# blous-afich.net
KiCad netlist of a schematic drawn in EAGLE
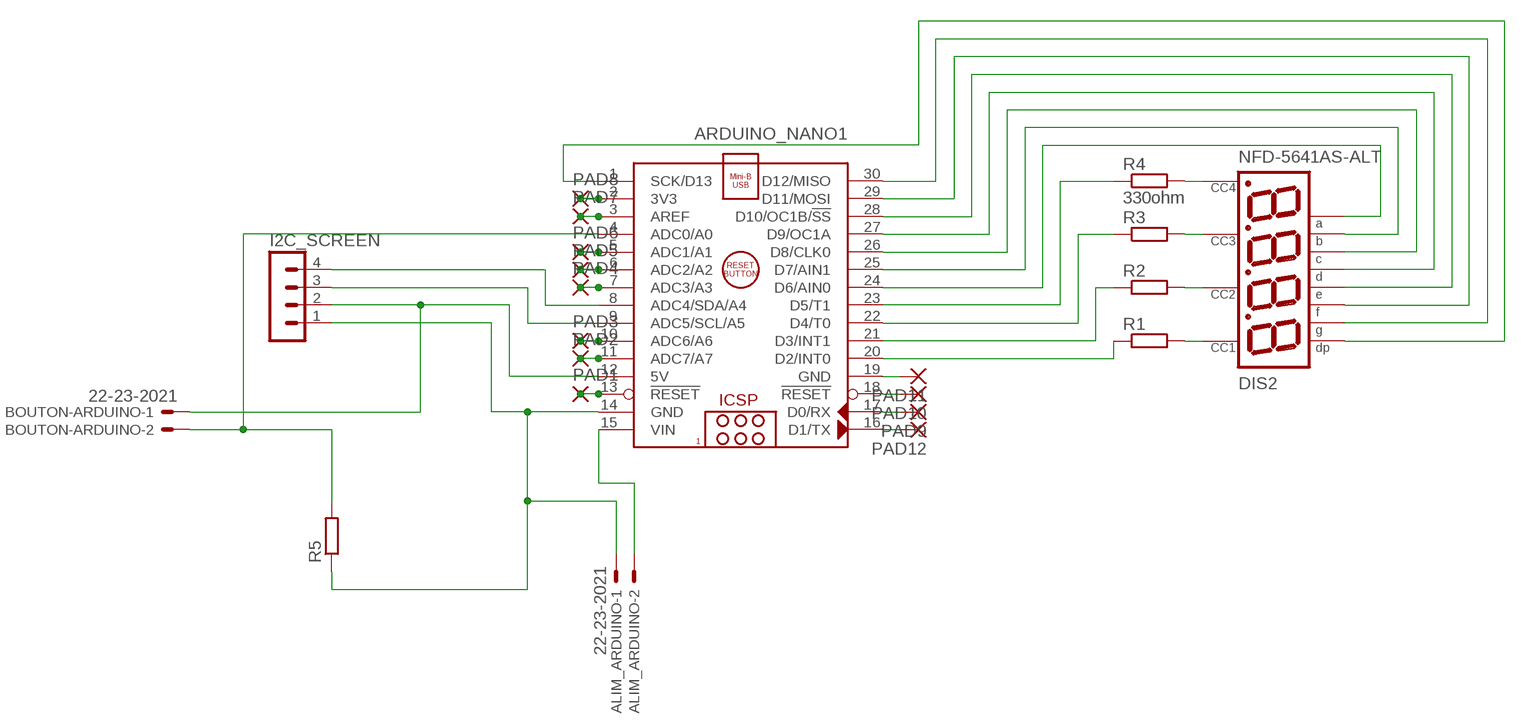
[diagram p0: schematic, sheet 1]

(export (version "E")
  (design (tool "Eeschema 10.0.6"))
  (components
    (comp (ref "ALIM_ARDUINO")
      (value "22-23-2021")
      (footprint "eagle-import:22-23-2021")
      (fields (field (name "MF") "MOLEX"))
      (libsource (lib "eagle-import") (part "22-23-2021"))
    )
    (comp (ref "ARDUINO_NANO1")
      (value "ARDUINO_NANO")
      (footprint "eagle-import:ARDUINO_NANO")
      (libsource (lib "eagle-import") (part "ARDUINO_NANO"))
    )
    (comp (ref "BOUTON-ARDUINO")
      (value "22-23-2021")
      (footprint "eagle-import:22-23-2021")
      (fields (field (name "MF") "MOLEX"))
      (libsource (lib "eagle-import") (part "22-23-2021"))
    )
    (comp (ref "DIS2")
      (value "NFD-5641AS-ALT")
      (footprint "eagle-import:NFD-5641")
      (libsource (lib "eagle-import") (part "NFD-5641AS-ALT"))
    )
    (comp (ref "I2C_SCREEN")
      (value "MA04-1")
      (footprint "eagle-import:MA04-1")
      (libsource (lib "eagle-import") (part "MA04-1"))
    )
    (comp (ref "PAD1")
      (value "1,6/0,8")
      (footprint "eagle-import:1,6_0,8")
      (libsource (lib "eagle-import") (part "1,6/0,8"))
    )
    (comp (ref "PAD2")
      (value "1,6/0,8")
      (footprint "eagle-import:1,6_0,8")
      (libsource (lib "eagle-import") (part "1,6/0,8"))
    )
    (comp (ref "PAD3")
      (value "1,6/0,8")
      (footprint "eagle-import:1,6_0,8")
      (libsource (lib "eagle-import") (part "1,6/0,8"))
    )
    (comp (ref "PAD4")
      (value "1,6/0,8")
      (footprint "eagle-import:1,6_0,8")
      (libsource (lib "eagle-import") (part "1,6/0,8"))
    )
    (comp (ref "PAD5")
      (value "1,6/0,8")
      (footprint "eagle-import:1,6_0,8")
      (libsource (lib "eagle-import") (part "1,6/0,8"))
    )
    (comp (ref "PAD6")
      (value "1,6/0,8")
      (footprint "eagle-import:1,6_0,8")
      (libsource (lib "eagle-import") (part "1,6/0,8"))
    )
    (comp (ref "PAD7")
      (value "1,6/0,8")
      (footprint "eagle-import:1,6_0,8")
      (libsource (lib "eagle-import") (part "1,6/0,8"))
    )
    (comp (ref "PAD8")
      (value "1,6/0,8")
      (footprint "eagle-import:1,6_0,8")
      (libsource (lib "eagle-import") (part "1,6/0,8"))
    )
    (comp (ref "PAD9")
      (value "1,6/0,8")
      (footprint "eagle-import:1,6_0,8")
      (libsource (lib "eagle-import") (part "1,6/0,8"))
    )
    (comp (ref "PAD10")
      (value "1,6/0,8")
      (footprint "eagle-import:1,6_0,8")
      (libsource (lib "eagle-import") (part "1,6/0,8"))
    )
    (comp (ref "PAD11")
      (value "1,6/0,8")
      (footprint "eagle-import:1,6_0,8")
      (libsource (lib "eagle-import") (part "1,6/0,8"))
    )
    (comp (ref "PAD12")
      (value "1,6/0,8")
      (footprint "eagle-import:1,6_0,8")
      (libsource (lib "eagle-import") (part "1,6/0,8"))
    )
    (comp (ref "R1")
      (value "R-EU_0207/7")
      (footprint "eagle-import:0207_7")
      (libsource (lib "eagle-import") (part "R-EU_0207/7"))
    )
    (comp (ref "R2")
      (value "R-EU_0207/7")
      (footprint "eagle-import:0207_7")
      (libsource (lib "eagle-import") (part "R-EU_0207/7"))
    )
    (comp (ref "R3")
      (value "R-EU_0207/7")
      (footprint "eagle-import:0207_7")
      (libsource (lib "eagle-import") (part "R-EU_0207/7"))
    )
    (comp (ref "R4")
      (value "330ohm")
      (footprint "eagle-import:0207_7")
      (libsource (lib "eagle-import") (part "R-EU_0207/7"))
    )
    (comp (ref "R5")
      (value "R-EU_0207/7")
      (footprint "eagle-import:0207_7")
      (libsource (lib "eagle-import") (part "R-EU_0207/7"))
    )
  )
  (nets
    (net (code "1") (name "Net-(ALIM_ARDUINOA-S)") (class "Default")
      (node (ref "ALIM_ARDUINO") (pin "1") (pinfunction "S_1") (pintype "passive"))
      (node (ref "ARDUINO_NANO1") (pin "14") (pinfunction "GND_14") (pintype "power_in"))
      (node (ref "I2C_SCREEN") (pin "1") (pinfunction "1_1") (pintype "passive"))
      (node (ref "R5") (pin "1") (pinfunction "1_1") (pintype "passive"))
    )
    (net (code "2") (name "Net-(ALIM_ARDUINOB-S)") (class "Default")
      (node (ref "ALIM_ARDUINO") (pin "2") (pinfunction "S_2") (pintype "passive"))
      (node (ref "ARDUINO_NANO1") (pin "15") (pinfunction "VIN_15") (pintype "power_in"))
    )
    (net (code "3") (name "Net-(ARDUINO_NANO1-3V3)") (class "Default")
      (node (ref "ARDUINO_NANO1") (pin "2") (pinfunction "3V3_2") (pintype "output"))
      (node (ref "PAD8") (pin "1") (pinfunction "P_1") (pintype "passive"))
    )
    (net (code "4") (name "Net-(ARDUINO_NANO1-5V)") (class "Default")
      (node (ref "ARDUINO_NANO1") (pin "12") (pinfunction "5V_12") (pintype "power_in"))
      (node (ref "BOUTON-ARDUINO") (pin "1") (pinfunction "S_1") (pintype "passive"))
      (node (ref "I2C_SCREEN") (pin "2") (pinfunction "2_2") (pintype "passive"))
    )
    (net (code "5") (name "Net-(ARDUINO_NANO1-ADC0{slash}A0)") (class "Default")
      (node (ref "ARDUINO_NANO1") (pin "4") (pinfunction "ADC0/A0_4") (pintype "bidirectional"))
      (node (ref "BOUTON-ARDUINO") (pin "2") (pinfunction "S_2") (pintype "passive"))
      (node (ref "R5") (pin "2") (pinfunction "2_2") (pintype "passive"))
    )
    (net (code "6") (name "Net-(ARDUINO_NANO1-ADC1{slash}A1)") (class "Default")
      (node (ref "ARDUINO_NANO1") (pin "5") (pinfunction "ADC1/A1_5") (pintype "bidirectional"))
      (node (ref "PAD6") (pin "1") (pinfunction "P_1") (pintype "passive"))
    )
    (net (code "7") (name "Net-(ARDUINO_NANO1-ADC2{slash}A2)") (class "Default")
      (node (ref "ARDUINO_NANO1") (pin "6") (pinfunction "ADC2/A2_6") (pintype "bidirectional"))
      (node (ref "PAD5") (pin "1") (pinfunction "P_1") (pintype "passive"))
    )
    (net (code "8") (name "Net-(ARDUINO_NANO1-ADC3{slash}A3)") (class "Default")
      (node (ref "ARDUINO_NANO1") (pin "7") (pinfunction "ADC3/A3_7") (pintype "bidirectional"))
      (node (ref "PAD4") (pin "1") (pinfunction "P_1") (pintype "passive"))
    )
    (net (code "9") (name "Net-(ARDUINO_NANO1-ADC4{slash}SDA{slash}A4)") (class "Default")
      (node (ref "ARDUINO_NANO1") (pin "8") (pinfunction "ADC4/SDA/A4_8") (pintype "bidirectional"))
      (node (ref "I2C_SCREEN") (pin "4") (pinfunction "4_4") (pintype "passive"))
    )
    (net (code "10") (name "Net-(ARDUINO_NANO1-ADC5{slash}SCL{slash}A5)") (class "Default")
      (node (ref "ARDUINO_NANO1") (pin "9") (pinfunction "ADC5/SCL/A5_9") (pintype "bidirectional"))
      (node (ref "I2C_SCREEN") (pin "3") (pinfunction "3_3") (pintype "passive"))
    )
    (net (code "11") (name "Net-(ARDUINO_NANO1-ADC6{slash}A6)") (class "Default")
      (node (ref "ARDUINO_NANO1") (pin "10") (pinfunction "ADC6/A6_10") (pintype "bidirectional"))
      (node (ref "PAD3") (pin "1") (pinfunction "P_1") (pintype "passive"))
    )
    (net (code "12") (name "Net-(ARDUINO_NANO1-ADC7{slash}A7)") (class "Default")
      (node (ref "ARDUINO_NANO1") (pin "11") (pinfunction "ADC7/A7_11") (pintype "bidirectional"))
      (node (ref "PAD2") (pin "1") (pinfunction "P_1") (pintype "passive"))
    )
    (net (code "13") (name "Net-(ARDUINO_NANO1-AREF)") (class "Default")
      (node (ref "ARDUINO_NANO1") (pin "3") (pinfunction "AREF_3") (pintype "input"))
      (node (ref "PAD7") (pin "1") (pinfunction "P_1") (pintype "passive"))
    )
    (net (code "14") (name "Net-(ARDUINO_NANO1-D0{slash}RX)") (class "Default")
      (node (ref "ARDUINO_NANO1") (pin "17") (pinfunction "D0/RX_17") (pintype "bidirectional"))
      (node (ref "PAD9") (pin "1") (pinfunction "P_1") (pintype "passive"))
    )
    (net (code "15") (name "Net-(ARDUINO_NANO1-D1{slash}TX)") (class "Default")
      (node (ref "ARDUINO_NANO1") (pin "16") (pinfunction "D1/TX_16") (pintype "bidirectional"))
      (node (ref "PAD12") (pin "1") (pinfunction "P_1") (pintype "passive"))
    )
    (net (code "16") (name "Net-(ARDUINO_NANO1-D2{slash}INT0)") (class "Default")
      (node (ref "ARDUINO_NANO1") (pin "20") (pinfunction "D2/INT0_20") (pintype "bidirectional"))
      (node (ref "R1") (pin "1") (pinfunction "1_1") (pintype "passive"))
    )
    (net (code "17") (name "Net-(ARDUINO_NANO1-D3{slash}INT1)") (class "Default")
      (node (ref "ARDUINO_NANO1") (pin "21") (pinfunction "D3/INT1_21") (pintype "bidirectional"))
      (node (ref "R2") (pin "1") (pinfunction "1_1") (pintype "passive"))
    )
    (net (code "18") (name "Net-(ARDUINO_NANO1-D4{slash}T0)") (class "Default")
      (node (ref "ARDUINO_NANO1") (pin "22") (pinfunction "D4/T0_22") (pintype "bidirectional"))
      (node (ref "R3") (pin "1") (pinfunction "1_1") (pintype "passive"))
    )
    (net (code "19") (name "Net-(ARDUINO_NANO1-D5{slash}T1)") (class "Default")
      (node (ref "ARDUINO_NANO1") (pin "23") (pinfunction "D5/T1_23") (pintype "bidirectional"))
      (node (ref "R4") (pin "1") (pinfunction "1_1") (pintype "passive"))
    )
    (net (code "20") (name "Net-(ARDUINO_NANO1-D6{slash}AIN0)") (class "Default")
      (node (ref "ARDUINO_NANO1") (pin "24") (pinfunction "D6/AIN0_24") (pintype "bidirectional"))
      (node (ref "DIS2") (pin "P$11") (pinfunction "P$11_P$11") (pintype "bidirectional"))
    )
    (net (code "21") (name "Net-(ARDUINO_NANO1-D7{slash}AIN1)") (class "Default")
      (node (ref "ARDUINO_NANO1") (pin "25") (pinfunction "D7/AIN1_25") (pintype "bidirectional"))
      (node (ref "DIS2") (pin "P$7") (pinfunction "P$7_P$7") (pintype "bidirectional"))
    )
    (net (code "22") (name "Net-(ARDUINO_NANO1-D8{slash}CLK0)") (class "Default")
      (node (ref "ARDUINO_NANO1") (pin "26") (pinfunction "D8/CLK0_26") (pintype "bidirectional"))
      (node (ref "DIS2") (pin "P$4") (pinfunction "P$4_P$4") (pintype "bidirectional"))
    )
    (net (code "23") (name "Net-(ARDUINO_NANO1-D9{slash}OC1A)") (class "Default")
      (node (ref "ARDUINO_NANO1") (pin "27") (pinfunction "D9/OC1A_27") (pintype "bidirectional"))
      (node (ref "DIS2") (pin "P$2") (pinfunction "P$2_P$2") (pintype "bidirectional"))
    )
    (net (code "24") (name "Net-(ARDUINO_NANO1-D10{slash}OC1B{slash}~{SS})") (class "Default")
      (node (ref "ARDUINO_NANO1") (pin "28") (pinfunction "D10/OC1B/~{SS}_28") (pintype "bidirectional"))
      (node (ref "DIS2") (pin "P$1") (pinfunction "P$1_P$1") (pintype "bidirectional"))
    )
    (net (code "25") (name "Net-(ARDUINO_NANO1-D11{slash}MOSI)") (class "Default")
      (node (ref "ARDUINO_NANO1") (pin "29") (pinfunction "D11/MOSI_29") (pintype "bidirectional"))
      (node (ref "DIS2") (pin "P$10") (pinfunction "P$10_P$10") (pintype "bidirectional"))
    )
    (net (code "26") (name "Net-(ARDUINO_NANO1-D12{slash}MISO)") (class "Default")
      (node (ref "ARDUINO_NANO1") (pin "30") (pinfunction "D12/MISO_30") (pintype "bidirectional"))
      (node (ref "DIS2") (pin "P$5") (pinfunction "P$5_P$5") (pintype "bidirectional"))
    )
    (net (code "27") (name "Net-(ARDUINO_NANO1-SCK{slash}D13)") (class "Default")
      (node (ref "ARDUINO_NANO1") (pin "1") (pinfunction "SCK/D13_1") (pintype "bidirectional"))
      (node (ref "DIS2") (pin "P$3") (pinfunction "P$3_P$3") (pintype "bidirectional"))
    )
    (net (code "28") (name "Net-(DIS2-PadP$6)") (class "Default")
      (node (ref "DIS2") (pin "P$6") (pinfunction "P$6_P$6") (pintype "bidirectional"))
      (node (ref "R4") (pin "2") (pinfunction "2_2") (pintype "passive"))
    )
    (net (code "29") (name "Net-(DIS2-PadP$8)") (class "Default")
      (node (ref "DIS2") (pin "P$8") (pinfunction "P$8_P$8") (pintype "bidirectional"))
      (node (ref "R3") (pin "2") (pinfunction "2_2") (pintype "passive"))
    )
    (net (code "30") (name "Net-(DIS2-PadP$9)") (class "Default")
      (node (ref "DIS2") (pin "P$9") (pinfunction "P$9_P$9") (pintype "bidirectional"))
      (node (ref "R2") (pin "2") (pinfunction "2_2") (pintype "passive"))
    )
    (net (code "31") (name "Net-(DIS2-PadP$12)") (class "Default")
      (node (ref "DIS2") (pin "P$12") (pinfunction "P$12_P$12") (pintype "bidirectional"))
      (node (ref "R1") (pin "2") (pinfunction "2_2") (pintype "passive"))
    )
    (net (code "32") (name "Net-(PAD1-P)") (class "Default")
      (node (ref "ARDUINO_NANO1") (pin "13") (pinfunction "~{RESET}_13") (pintype "input"))
      (node (ref "PAD1") (pin "1") (pinfunction "P_1") (pintype "passive"))
    )
    (net (code "33") (name "Net-(PAD10-P)") (class "Default")
      (node (ref "ARDUINO_NANO1") (pin "18") (pinfunction "~{RESET}_18") (pintype "input"))
      (node (ref "PAD10") (pin "1") (pinfunction "P_1") (pintype "passive"))
    )
    (net (code "34") (name "Net-(PAD11-P)") (class "Default")
      (node (ref "ARDUINO_NANO1") (pin "19") (pinfunction "GND_19") (pintype "power_in"))
      (node (ref "PAD11") (pin "1") (pinfunction "P_1") (pintype "passive"))
    )
  )
)
